# Open_Reactor_Control_System_-_Machine_In.net
KiCad netlist of a schematic drawn in Altium Designer
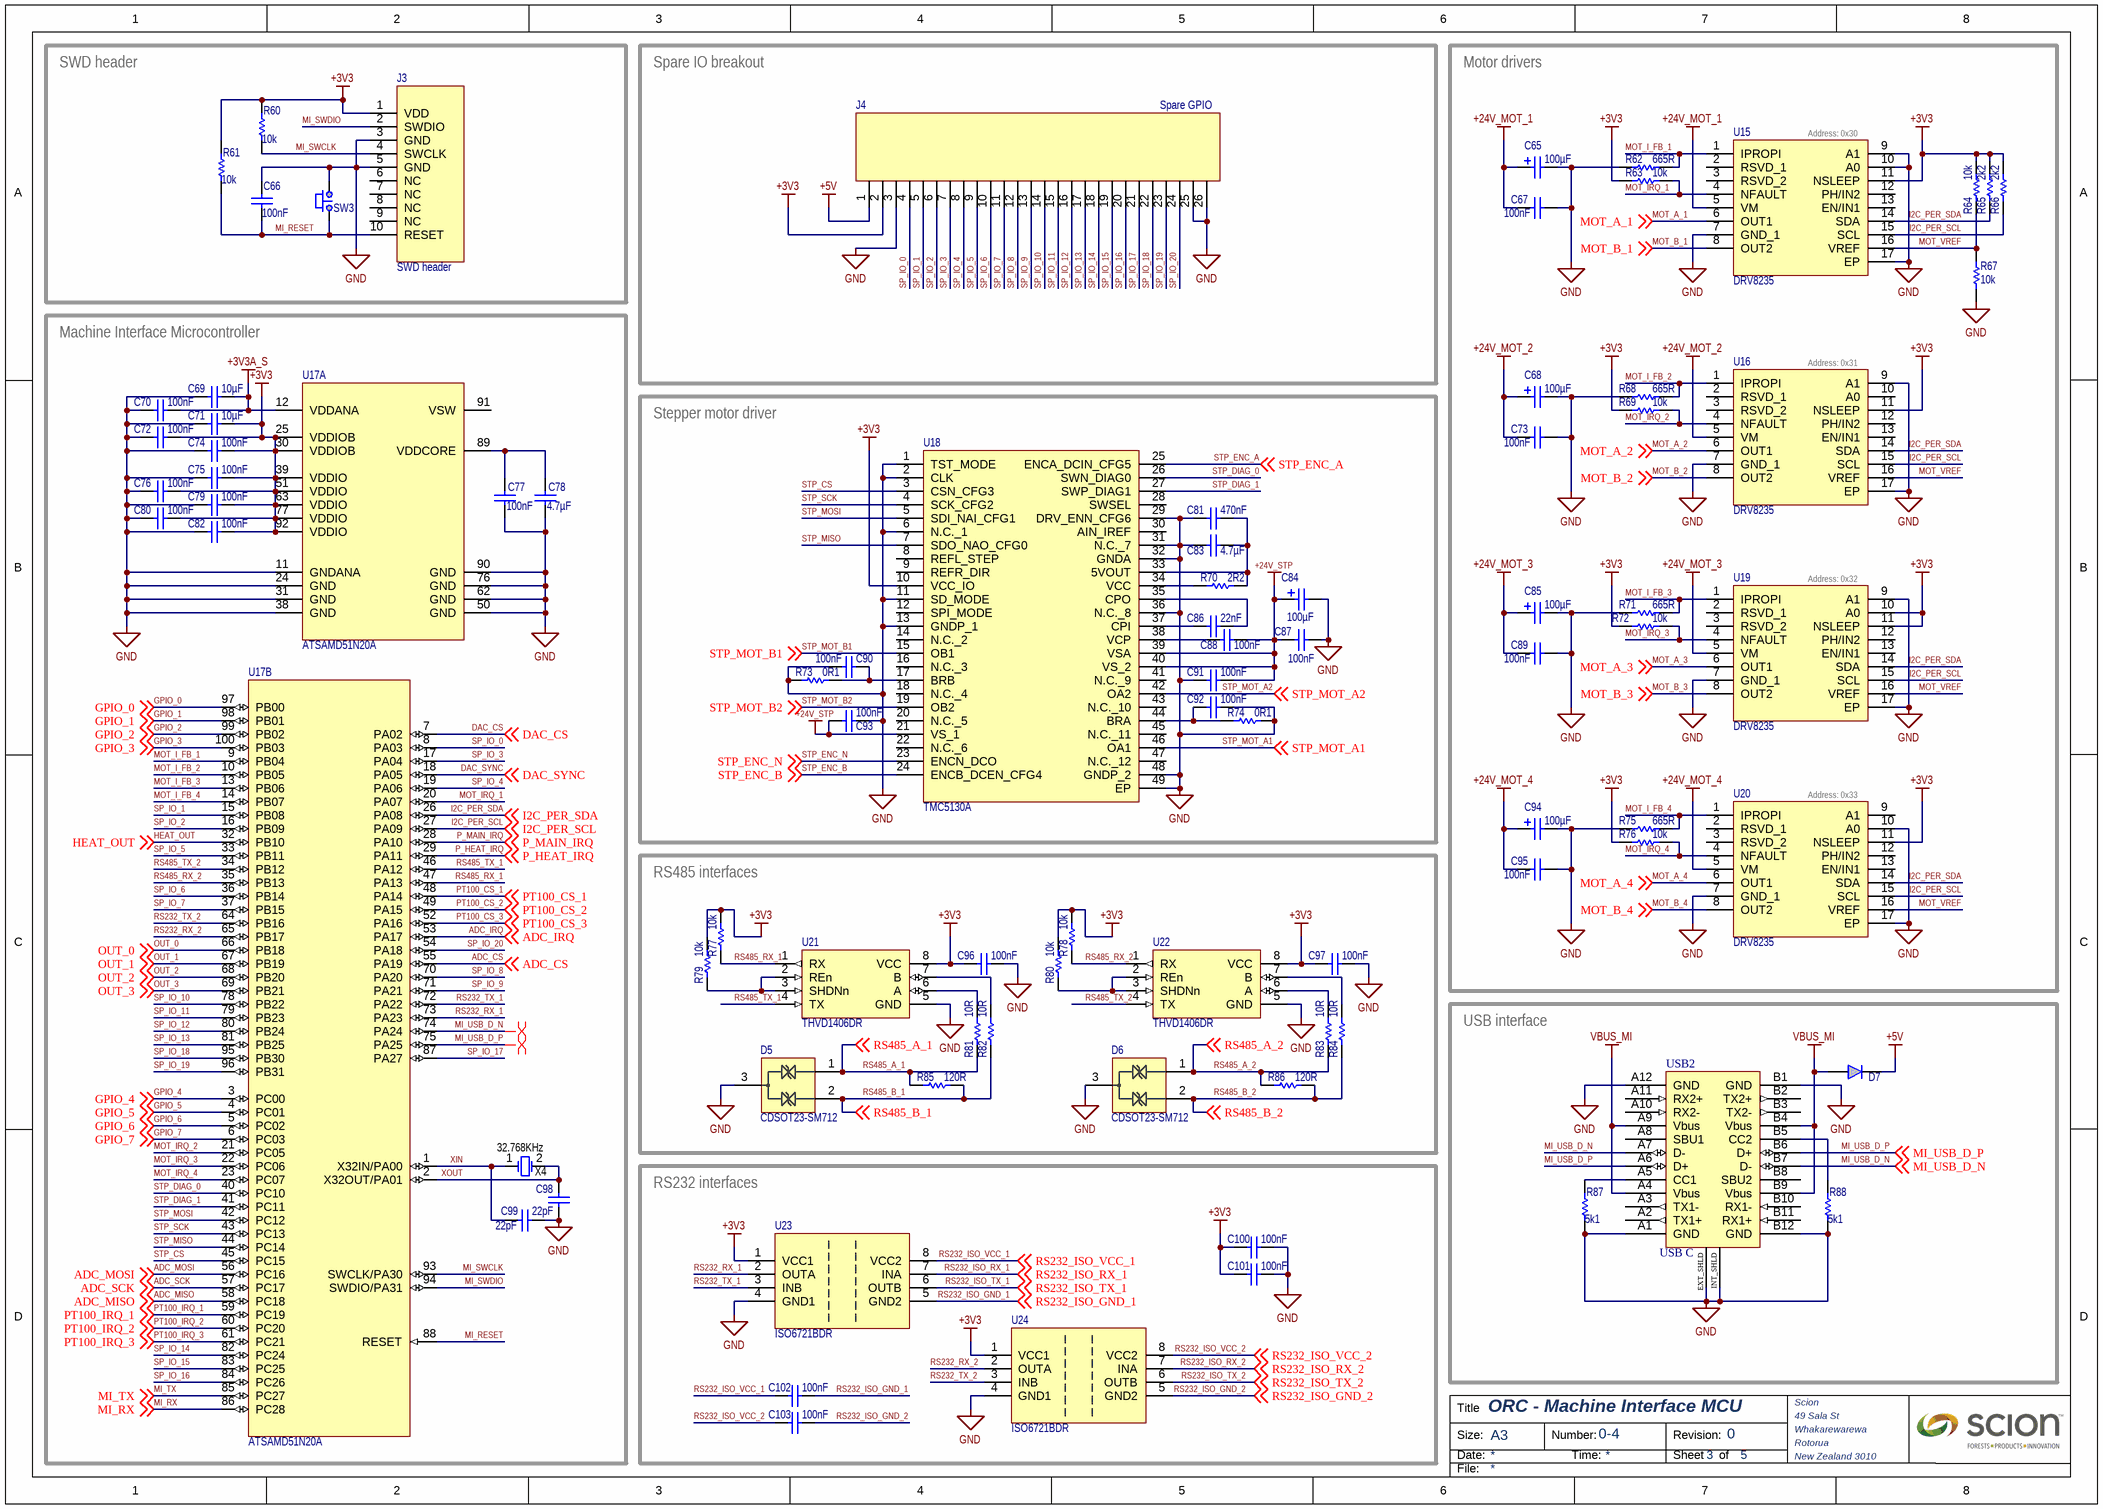
[diagram p0: Open Reactor Control System - Machine Interface MCU.SchDoc]

(export (version "E")
  (design (tool "Eeschema 10.0.6"))
  (components
    (comp (ref "C65")
      (value "Capacitor Electrolytic")
      (footprint "CAP_PANA_F12_SIZE")
      (description "SMD Electrolytic Capacitor")
      (fields (field (name "ALTIUM_VALUE") "100µF"))
      (libsource (lib "Scion Research") (part "CMP-001-00084-1"))
    )
    (comp (ref "C66")
      (value "100nF")
      (footprint "0603_CAP")
      (description "SMD Capacitor")
      (fields (field (name "Comment") "Capacitor"))
      (libsource (lib "Scion Research") (part "CMP-019-00005-2"))
    )
    (comp (ref "C67")
      (value "100nF")
      (footprint "0603_CAP")
      (description "SMD Capacitor")
      (fields (field (name "Comment") "Capacitor"))
      (libsource (lib "Scion Research") (part "CMP-019-00005-2"))
    )
    (comp (ref "C68")
      (value "Capacitor Electrolytic")
      (footprint "CAP_PANA_F12_SIZE")
      (description "SMD Electrolytic Capacitor")
      (fields (field (name "ALTIUM_VALUE") "100µF"))
      (libsource (lib "Scion Research") (part "CMP-001-00084-1"))
    )
    (comp (ref "C69")
      (value "10µF")
      (footprint "0603_CAP")
      (description "SMD Capacitor")
      (fields (field (name "Comment") "Capacitor"))
      (libsource (lib "Scion Research") (part "CMP-019-00005-2"))
    )
    (comp (ref "C70")
      (value "100nF")
      (footprint "0402_CAP")
      (description "SMD Capacitor")
      (fields (field (name "Comment") "Capacitor"))
      (libsource (lib "Scion Research") (part "CMP-019-00005-2"))
    )
    (comp (ref "C71")
      (value "10µF")
      (footprint "0603_CAP")
      (description "SMD Capacitor")
      (fields (field (name "Comment") "Capacitor"))
      (libsource (lib "Scion Research") (part "CMP-019-00005-2"))
    )
    (comp (ref "C72")
      (value "100nF")
      (footprint "0402_CAP")
      (description "SMD Capacitor")
      (fields (field (name "Comment") "Capacitor"))
      (libsource (lib "Scion Research") (part "CMP-019-00005-2"))
    )
    (comp (ref "C73")
      (value "100nF")
      (footprint "0603_CAP")
      (description "SMD Capacitor")
      (fields (field (name "Comment") "Capacitor"))
      (libsource (lib "Scion Research") (part "CMP-019-00005-2"))
    )
    (comp (ref "C74")
      (value "100nF")
      (footprint "0402_CAP")
      (description "SMD Capacitor")
      (fields (field (name "Comment") "Capacitor"))
      (libsource (lib "Scion Research") (part "CMP-019-00005-2"))
    )
    (comp (ref "C75")
      (value "100nF")
      (footprint "0402_CAP")
      (description "SMD Capacitor")
      (fields (field (name "Comment") "Capacitor"))
      (libsource (lib "Scion Research") (part "CMP-019-00005-2"))
    )
    (comp (ref "C76")
      (value "100nF")
      (footprint "0402_CAP")
      (description "SMD Capacitor")
      (fields (field (name "Comment") "Capacitor"))
      (libsource (lib "Scion Research") (part "CMP-019-00005-2"))
    )
    (comp (ref "C77")
      (value "100nF")
      (footprint "0402_CAP")
      (description "SMD Capacitor")
      (fields (field (name "Comment") "Capacitor"))
      (libsource (lib "Scion Research") (part "CMP-019-00005-2"))
    )
    (comp (ref "C78")
      (value "4.7µF")
      (footprint "0603_CAP")
      (description "SMD Capacitor")
      (fields (field (name "Comment") "Capacitor"))
      (libsource (lib "Scion Research") (part "CMP-019-00005-2"))
    )
    (comp (ref "C79")
      (value "100nF")
      (footprint "0402_CAP")
      (description "SMD Capacitor")
      (fields (field (name "Comment") "Capacitor"))
      (libsource (lib "Scion Research") (part "CMP-019-00005-2"))
    )
    (comp (ref "C80")
      (value "100nF")
      (footprint "0402_CAP")
      (description "SMD Capacitor")
      (fields (field (name "Comment") "Capacitor"))
      (libsource (lib "Scion Research") (part "CMP-019-00005-2"))
    )
    (comp (ref "C81")
      (value "470nF")
      (footprint "0603_CAP")
      (description "SMD Capacitor")
      (fields (field (name "Comment") "Capacitor"))
      (libsource (lib "Scion Research") (part "CMP-019-00005-2"))
    )
    (comp (ref "C82")
      (value "100nF")
      (footprint "0402_CAP")
      (description "SMD Capacitor")
      (fields (field (name "Comment") "Capacitor"))
      (libsource (lib "Scion Research") (part "CMP-019-00005-2"))
    )
    (comp (ref "C83")
      (value "4.7µF")
      (footprint "0603_CAP")
      (description "SMD Capacitor")
      (fields (field (name "Comment") "Capacitor"))
      (libsource (lib "Scion Research") (part "CMP-019-00005-2"))
    )
    (comp (ref "C84")
      (value "Capacitor Electrolytic")
      (footprint "CAP_PANA_F12_SIZE")
      (description "SMD Electrolytic Capacitor")
      (fields (field (name "ALTIUM_VALUE") "100µF"))
      (libsource (lib "Scion Research") (part "CMP-001-00084-1"))
    )
    (comp (ref "C85")
      (value "Capacitor Electrolytic")
      (footprint "CAP_PANA_F12_SIZE")
      (description "SMD Electrolytic Capacitor")
      (fields (field (name "ALTIUM_VALUE") "100µF"))
      (libsource (lib "Scion Research") (part "CMP-001-00084-1"))
    )
    (comp (ref "C86")
      (value "22nF")
      (footprint "0603_CAP")
      (description "SMD Capacitor")
      (fields (field (name "Comment") "Capacitor"))
      (libsource (lib "Scion Research") (part "CMP-019-00005-2"))
    )
    (comp (ref "C87")
      (value "100nF")
      (footprint "0603_CAP")
      (description "SMD Capacitor")
      (fields (field (name "Comment") "Capacitor"))
      (libsource (lib "Scion Research") (part "CMP-019-00005-2"))
    )
    (comp (ref "C88")
      (value "100nF")
      (footprint "0603_CAP")
      (description "SMD Capacitor")
      (fields (field (name "Comment") "Capacitor"))
      (libsource (lib "Scion Research") (part "CMP-019-00005-2"))
    )
    (comp (ref "C89")
      (value "100nF")
      (footprint "0603_CAP")
      (description "SMD Capacitor")
      (fields (field (name "Comment") "Capacitor"))
      (libsource (lib "Scion Research") (part "CMP-019-00005-2"))
    )
    (comp (ref "C90")
      (value "100nF")
      (footprint "0603_CAP")
      (description "SMD Capacitor")
      (fields (field (name "Comment") "Capacitor"))
      (libsource (lib "Scion Research") (part "CMP-019-00005-2"))
    )
    (comp (ref "C91")
      (value "100nF")
      (footprint "0603_CAP")
      (description "SMD Capacitor")
      (fields (field (name "Comment") "Capacitor"))
      (libsource (lib "Scion Research") (part "CMP-019-00005-2"))
    )
    (comp (ref "C92")
      (value "100nF")
      (footprint "0603_CAP")
      (description "SMD Capacitor")
      (fields (field (name "Comment") "Capacitor"))
      (libsource (lib "Scion Research") (part "CMP-019-00005-2"))
    )
    (comp (ref "C93")
      (value "100nF")
      (footprint "0603_CAP")
      (description "SMD Capacitor")
      (fields (field (name "Comment") "Capacitor"))
      (libsource (lib "Scion Research") (part "CMP-019-00005-2"))
    )
    (comp (ref "C94")
      (value "Capacitor Electrolytic")
      (footprint "CAP_PANA_F12_SIZE")
      (description "SMD Electrolytic Capacitor")
      (fields (field (name "ALTIUM_VALUE") "100µF"))
      (libsource (lib "Scion Research") (part "CMP-001-00084-1"))
    )
    (comp (ref "C95")
      (value "100nF")
      (footprint "0603_CAP")
      (description "SMD Capacitor")
      (fields (field (name "Comment") "Capacitor"))
      (libsource (lib "Scion Research") (part "CMP-019-00005-2"))
    )
    (comp (ref "C96")
      (value "100nF")
      (footprint "0603_CAP")
      (description "SMD Capacitor")
      (fields (field (name "Comment") "Capacitor"))
      (libsource (lib "Scion Research") (part "CMP-019-00005-2"))
    )
    (comp (ref "C97")
      (value "100nF")
      (footprint "0603_CAP")
      (description "SMD Capacitor")
      (fields (field (name "Comment") "Capacitor"))
      (libsource (lib "Scion Research") (part "CMP-019-00005-2"))
    )
    (comp (ref "C98")
      (value "22pF")
      (footprint "0402_CAP")
      (description "SMD Capacitor")
      (fields (field (name "Comment") "Capacitor"))
      (libsource (lib "Scion Research") (part "CMP-019-00005-2"))
    )
    (comp (ref "C99")
      (value "22pF")
      (footprint "0402_CAP")
      (description "SMD Capacitor")
      (fields (field (name "Comment") "Capacitor"))
      (libsource (lib "Scion Research") (part "CMP-019-00005-2"))
    )
    (comp (ref "C100")
      (value "100nF")
      (footprint "0603_CAP")
      (description "SMD Capacitor")
      (fields (field (name "Comment") "Capacitor"))
      (libsource (lib "Scion Research") (part "CMP-019-00005-2"))
    )
    (comp (ref "C101")
      (value "100nF")
      (footprint "0603_CAP")
      (description "SMD Capacitor")
      (fields (field (name "Comment") "Capacitor"))
      (libsource (lib "Scion Research") (part "CMP-019-00005-2"))
    )
    (comp (ref "C102")
      (value "100nF")
      (footprint "0603_CAP")
      (description "SMD Capacitor")
      (fields (field (name "Comment") "Capacitor"))
      (libsource (lib "Scion Research") (part "CMP-019-00005-2"))
    )
    (comp (ref "C103")
      (value "100nF")
      (footprint "0603_CAP")
      (description "SMD Capacitor")
      (fields (field (name "Comment") "Capacitor"))
      (libsource (lib "Scion Research") (part "CMP-019-00005-2"))
    )
    (comp (ref "D5")
      (value "CDSOT23-SM712")
      (footprint "FP-SOT23-IPC_C")
      (description "Trans Voltage Suppressor Diode, 400W, 7V V(RWM), Bidirectional, 2 Element, Silicon")
      (libsource (lib "Scion Research") (part "CDSOT23-SM712"))
    )
    (comp (ref "D6")
      (value "CDSOT23-SM712")
      (footprint "FP-SOT23-IPC_C")
      (description "Trans Voltage Suppressor Diode, 400W, 7V V(RWM), Bidirectional, 2 Element, Silicon")
      (libsource (lib "Scion Research") (part "CDSOT23-SM712"))
    )
    (comp (ref "D7")
      (value "Diode")
      (footprint "SOD-123")
      (description "SMD Diode")
      (libsource (lib "Scion Research") (part "Diode"))
    )
    (comp (ref "J3")
      (value "SWD header")
      (footprint "DIP10_1.27_M_SMD")
      (description "10 Pin Connector")
      (libsource (lib "Scion Research") (part "CMP-002-00071-2"))
    )
    (comp (ref "J4")
      (value "Spare GPIO")
      (footprint "26_Pin DIL Male Header 2.54mm")
      (description "26 Pin Connector")
      (libsource (lib "Scion Research") (part "26 Pin Connector"))
    )
    (comp (ref "R60")
      (value "Resistor")
      (footprint "0603_RES")
      (description "SMD Resistor")
      (fields (field (name "ALTIUM_VALUE") "10k"))
      (libsource (lib "Scion Research") (part "CMP-009-00177-2"))
    )
    (comp (ref "R61")
      (value "Resistor")
      (footprint "0603_RES")
      (description "SMD Resistor")
      (fields (field (name "ALTIUM_VALUE") "10k"))
      (libsource (lib "Scion Research") (part "CMP-009-00177-2"))
    )
    (comp (ref "R62")
      (value "Resistor")
      (footprint "0603_RES")
      (description "SMD Resistor")
      (fields (field (name "ALTIUM_VALUE") "665R"))
      (libsource (lib "Scion Research") (part "CMP-009-00177-2"))
    )
    (comp (ref "R63")
      (value "Resistor")
      (footprint "0603_RES")
      (description "SMD Resistor")
      (fields (field (name "ALTIUM_VALUE") "10k"))
      (libsource (lib "Scion Research") (part "CMP-009-00177-2"))
    )
    (comp (ref "R64")
      (value "Resistor")
      (footprint "0603_RES")
      (description "SMD Resistor")
      (fields (field (name "ALTIUM_VALUE") "10k"))
      (libsource (lib "Scion Research") (part "CMP-009-00177-2"))
    )
    (comp (ref "R65")
      (value "Resistor")
      (footprint "0603_RES")
      (description "SMD Resistor")
      (fields (field (name "ALTIUM_VALUE") "2k2"))
      (libsource (lib "Scion Research") (part "CMP-009-00177-2"))
    )
    (comp (ref "R66")
      (value "Resistor")
      (footprint "0603_RES")
      (description "SMD Resistor")
      (fields (field (name "ALTIUM_VALUE") "2k2"))
      (libsource (lib "Scion Research") (part "CMP-009-00177-2"))
    )
    (comp (ref "R67")
      (value "Resistor")
      (footprint "0603_RES")
      (description "SMD Resistor")
      (fields (field (name "ALTIUM_VALUE") "10k"))
      (libsource (lib "Scion Research") (part "CMP-009-00177-2"))
    )
    (comp (ref "R68")
      (value "Resistor")
      (footprint "0603_RES")
      (description "SMD Resistor")
      (fields (field (name "ALTIUM_VALUE") "665R"))
      (libsource (lib "Scion Research") (part "CMP-009-00177-2"))
    )
    (comp (ref "R69")
      (value "Resistor")
      (footprint "0603_RES")
      (description "SMD Resistor")
      (fields (field (name "ALTIUM_VALUE") "10k"))
      (libsource (lib "Scion Research") (part "CMP-009-00177-2"))
    )
    (comp (ref "R70")
      (value "Resistor")
      (footprint "0603_RES")
      (description "SMD Resistor")
      (fields (field (name "ALTIUM_VALUE") "2R2"))
      (libsource (lib "Scion Research") (part "CMP-009-00177-2"))
    )
    (comp (ref "R71")
      (value "Resistor")
      (footprint "0603_RES")
      (description "SMD Resistor")
      (fields (field (name "ALTIUM_VALUE") "665R"))
      (libsource (lib "Scion Research") (part "CMP-009-00177-2"))
    )
    (comp (ref "R72")
      (value "Resistor")
      (footprint "0603_RES")
      (description "SMD Resistor")
      (fields (field (name "ALTIUM_VALUE") "10k"))
      (libsource (lib "Scion Research") (part "CMP-009-00177-2"))
    )
    (comp (ref "R73")
      (value "Resistor")
      (footprint "1206_RES")
      (description "SMD Resistor")
      (fields (field (name "ALTIUM_VALUE") "0R1"))
      (libsource (lib "Scion Research") (part "CMP-009-00177-2"))
    )
    (comp (ref "R74")
      (value "Resistor")
      (footprint "1206_RES")
      (description "SMD Resistor")
      (fields (field (name "ALTIUM_VALUE") "0R1"))
      (libsource (lib "Scion Research") (part "CMP-009-00177-2"))
    )
    (comp (ref "R75")
      (value "Resistor")
      (footprint "0603_RES")
      (description "SMD Resistor")
      (fields (field (name "ALTIUM_VALUE") "665R"))
      (libsource (lib "Scion Research") (part "CMP-009-00177-2"))
    )
    (comp (ref "R76")
      (value "Resistor")
      (footprint "0603_RES")
      (description "SMD Resistor")
      (fields (field (name "ALTIUM_VALUE") "10k"))
      (libsource (lib "Scion Research") (part "CMP-009-00177-2"))
    )
    (comp (ref "R77")
      (value "Resistor")
      (footprint "0603_RES")
      (description "SMD Resistor")
      (fields (field (name "ALTIUM_VALUE") "10k"))
      (libsource (lib "Scion Research") (part "CMP-009-00177-2"))
    )
    (comp (ref "R78")
      (value "Resistor")
      (footprint "0603_RES")
      (description "SMD Resistor")
      (fields (field (name "ALTIUM_VALUE") "10k"))
      (libsource (lib "Scion Research") (part "CMP-009-00177-2"))
    )
    (comp (ref "R79")
      (value "Resistor")
      (footprint "0603_RES")
      (description "SMD Resistor")
      (fields (field (name "ALTIUM_VALUE") "10k"))
      (libsource (lib "Scion Research") (part "CMP-009-00177-2"))
    )
    (comp (ref "R80")
      (value "Resistor")
      (footprint "0603_RES")
      (description "SMD Resistor")
      (fields (field (name "ALTIUM_VALUE") "10k"))
      (libsource (lib "Scion Research") (part "CMP-009-00177-2"))
    )
    (comp (ref "R81")
      (value "Resistor")
      (footprint "0603_RES")
      (description "SMD Resistor")
      (fields (field (name "ALTIUM_VALUE") "10R"))
      (libsource (lib "Scion Research") (part "CMP-009-00177-2"))
    )
    (comp (ref "R82")
      (value "Resistor")
      (footprint "0603_RES")
      (description "SMD Resistor")
      (fields (field (name "ALTIUM_VALUE") "10R"))
      (libsource (lib "Scion Research") (part "CMP-009-00177-2"))
    )
    (comp (ref "R83")
      (value "Resistor")
      (footprint "0603_RES")
      (description "SMD Resistor")
      (fields (field (name "ALTIUM_VALUE") "10R"))
      (libsource (lib "Scion Research") (part "CMP-009-00177-2"))
    )
    (comp (ref "R84")
      (value "Resistor")
      (footprint "0603_RES")
      (description "SMD Resistor")
      (fields (field (name "ALTIUM_VALUE") "10R"))
      (libsource (lib "Scion Research") (part "CMP-009-00177-2"))
    )
    (comp (ref "R85")
      (value "Resistor")
      (footprint "0603_RES")
      (description "SMD Resistor")
      (fields (field (name "ALTIUM_VALUE") "120R"))
      (libsource (lib "Scion Research") (part "CMP-009-00177-2"))
    )
    (comp (ref "R86")
      (value "Resistor")
      (footprint "0603_RES")
      (description "SMD Resistor")
      (fields (field (name "ALTIUM_VALUE") "120R"))
      (libsource (lib "Scion Research") (part "CMP-009-00177-2"))
    )
    (comp (ref "R87")
      (value "Resistor")
      (footprint "0603_RES")
      (description "SMD Resistor")
      (fields (field (name "ALTIUM_VALUE") "5k1"))
      (libsource (lib "Scion Research") (part "CMP-009-00177-2"))
    )
    (comp (ref "R88")
      (value "Resistor")
      (footprint "0603_RES")
      (description "SMD Resistor")
      (fields (field (name "ALTIUM_VALUE") "5k1"))
      (libsource (lib "Scion Research") (part "CMP-009-00177-2"))
    )
    (comp (ref "SW3")
      (value "EVP-AAN02Q")
      (footprint "FP-EVP-AAN02Q-MFG")
      (description "Switch Tactile N.O. SPST Rectangular Button J-Bend 0.02A 15VDC 100000Cycles 5N SMD T/R")
      (libsource (lib "Scion Research") (part "67890d47754ac483cb1d3ba3be74b6c"))
    )
    (comp (ref "U15")
      (value "DRV8235")
      (footprint "DRV8235-Footprint-1")
      (libsource (lib "Scion Research") (part "DRV8235-Symbol-1"))
    )
    (comp (ref "U16")
      (value "DRV8235")
      (footprint "DRV8235-Footprint-1")
      (libsource (lib "Scion Research") (part "DRV8235-Symbol-1"))
    )
    (comp (ref "U17")
      (value "ATSAMD51N20A")
      (footprint "FP-C04-110-IPC_C")
      (description "RISC Microcontroller, 32-Bit, FLASH, 120MHz, CMOS, PQFP100")
      (libsource (lib "Scion Research") (part "ATSAMD51N20A-AU-Symbol-1"))
    )
    (comp (ref "U18")
      (value "TMC5130A")
      (footprint "TMC5130A-Footprint-1")
      (libsource (lib "Scion Research") (part "TMC5130A-Symbol-1"))
    )
    (comp (ref "U19")
      (value "DRV8235")
      (footprint "DRV8235-Footprint-1")
      (libsource (lib "Scion Research") (part "DRV8235-Symbol-1"))
    )
    (comp (ref "U20")
      (value "DRV8235")
      (footprint "DRV8235-Footprint-1")
      (libsource (lib "Scion Research") (part "DRV8235-Symbol-1"))
    )
    (comp (ref "U21")
      (value "THVD1406DR")
      (footprint "SOIC127P600X175-8N")
      (description "Line Transceiver, 1 Func, 1 Driver, 1 Rcvr, PDSO8")
      (libsource (lib "Scion Research") (part "THVD1406DR-Symbol-1"))
    )
    (comp (ref "U22")
      (value "THVD1406DR")
      (footprint "SOIC127P600X175-8N")
      (description "Line Transceiver, 1 Func, 1 Driver, 1 Rcvr, PDSO8")
      (libsource (lib "Scion Research") (part "THVD1406DR-Symbol-1"))
    )
    (comp (ref "U23")
      (value "ISO6721BDR")
      (footprint "SOIC127P600X175-8N")
      (description "Interface Circuit, CMOS, PDSO8")
      (libsource (lib "Scion Research") (part "ISO6721BDR-Symbol-1"))
    )
    (comp (ref "U24")
      (value "ISO6721BDR")
      (footprint "SOIC127P600X175-8N")
      (description "Interface Circuit, CMOS, PDSO8")
      (libsource (lib "Scion Research") (part "ISO6721BDR-Symbol-1"))
    )
    (comp (ref "USB2")
      (value "USB C")
      (footprint "GT-USB-7010ASV")
      (description "Vertical or RA Type C Usb Connector Rohs Compliant: Yes")
      (libsource (lib "Scion Research") (part "CMP-00005-5"))
    )
    (comp (ref "X4")
      (value "32.768KHz")
      (footprint "ABRA-ABS07-2_V")
      (fields (field (name "TOLERANCE") "20ppm") (field (name "MANUFACTURER") "Abracon"))
      (libsource (lib "Scion Research") (part "CMP-003-00022-1"))
    )
  )
  (nets
    (net (code "1") (name "+3V3") (class "Default")
      (node (ref "C100") (pin "2") (pinfunction "2_2") (pintype "passive"))
      (node (ref "C101") (pin "2") (pinfunction "2_2") (pintype "passive"))
      (node (ref "C71") (pin "1") (pinfunction "1_1") (pintype "passive"))
      (node (ref "C72") (pin "1") (pinfunction "1_1") (pintype "passive"))
      (node (ref "C74") (pin "1") (pinfunction "1_1") (pintype "passive"))
      (node (ref "C75") (pin "1") (pinfunction "1_1") (pintype "passive"))
      (node (ref "C76") (pin "1") (pinfunction "1_1") (pintype "passive"))
      (node (ref "C79") (pin "1") (pinfunction "1_1") (pintype "passive"))
      (node (ref "C80") (pin "1") (pinfunction "1_1") (pintype "passive"))
      (node (ref "C82") (pin "1") (pinfunction "1_1") (pintype "passive"))
      (node (ref "C96") (pin "2") (pinfunction "2_2") (pintype "passive"))
      (node (ref "C97") (pin "2") (pinfunction "2_2") (pintype "passive"))
      (node (ref "J3") (pin "1") (pinfunction "VDD_1") (pintype "passive"))
      (node (ref "J4") (pin "2") (pinfunction "2_2") (pintype "passive"))
      (node (ref "R60") (pin "1") (pinfunction "1_1") (pintype "passive"))
      (node (ref "R61") (pin "1") (pinfunction "1_1") (pintype "passive"))
      (node (ref "R63") (pin "2") (pinfunction "2_2") (pintype "passive"))
      (node (ref "R64") (pin "2") (pinfunction "2_2") (pintype "passive"))
      (node (ref "R65") (pin "1") (pinfunction "1_1") (pintype "passive"))
      (node (ref "R66") (pin "1") (pinfunction "1_1") (pintype "passive"))
      (node (ref "R69") (pin "2") (pinfunction "2_2") (pintype "passive"))
      (node (ref "R72") (pin "2") (pinfunction "2_2") (pintype "passive"))
      (node (ref "R76") (pin "2") (pinfunction "2_2") (pintype "passive"))
      (node (ref "R77") (pin "1") (pinfunction "1_1") (pintype "passive"))
      (node (ref "R78") (pin "1") (pinfunction "1_1") (pintype "passive"))
      (node (ref "R79") (pin "1") (pinfunction "1_1") (pintype "passive"))
      (node (ref "R80") (pin "1") (pinfunction "1_1") (pintype "passive"))
      (node (ref "U15") (pin "11") (pinfunction "NSLEEP_11") (pintype "passive"))
      (node (ref "U16") (pin "11") (pinfunction "NSLEEP_11") (pintype "passive"))
      (node (ref "U17") (pin "25") (pinfunction "VDDIOB_25") (pintype "power_in"))
      (node (ref "U17") (pin "30") (pinfunction "VDDIOB_30") (pintype "power_in"))
      (node (ref "U17") (pin "39") (pinfunction "VDDIO_39") (pintype "power_in"))
      (node (ref "U17") (pin "51") (pinfunction "VDDIO_51") (pintype "power_in"))
      (node (ref "U17") (pin "63") (pinfunction "VDDIO_63") (pintype "power_in"))
      (node (ref "U17") (pin "77") (pinfunction "VDDIO_77") (pintype "power_in"))
      (node (ref "U17") (pin "92") (pinfunction "VDDIO_92") (pintype "power_in"))
      (node (ref "U18") (pin "10") (pinfunction "VCC_IO_10") (pintype "passive"))
      (node (ref "U19") (pin "10") (pinfunction "A0_10") (pintype "passive"))
      (node (ref "U19") (pin "11") (pinfunction "NSLEEP_11") (pintype "passive"))
      (node (ref "U20") (pin "11") (pinfunction "NSLEEP_11") (pintype "passive"))
      (node (ref "U21") (pin "8") (pinfunction "VCC_8") (pintype "power_in"))
      (node (ref "U22") (pin "8") (pinfunction "VCC_8") (pintype "power_in"))
      (node (ref "U23") (pin "1") (pinfunction "VCC1_1") (pintype "passive"))
      (node (ref "U24") (pin "1") (pinfunction "VCC1_1") (pintype "passive"))
    )
    (net (code "2") (name "+3V3A_S") (class "Default")
      (node (ref "C69") (pin "1") (pinfunction "1_1") (pintype "passive"))
      (node (ref "C70") (pin "1") (pinfunction "1_1") (pintype "passive"))
      (node (ref "U17") (pin "12") (pinfunction "VDDANA_12") (pintype "power_in"))
    )
    (net (code "3") (name "+5V") (class "Default")
      (node (ref "D7") (pin "1") (pinfunction "K_1") (pintype "passive"))
      (node (ref "J4") (pin "1") (pinfunction "1_1") (pintype "passive"))
    )
    (net (code "4") (name "+24V_MOT_1") (class "Default")
      (node (ref "C65") (pin "1") (pinfunction "1_1") (pintype "passive"))
      (node (ref "C67") (pin "1") (pinfunction "1_1") (pintype "passive"))
      (node (ref "U15") (pin "5") (pinfunction "VM_5") (pintype "passive"))
    )
    (net (code "5") (name "+24V_MOT_2") (class "Default")
      (node (ref "C68") (pin "1") (pinfunction "1_1") (pintype "passive"))
      (node (ref "C73") (pin "1") (pinfunction "1_1") (pintype "passive"))
      (node (ref "U16") (pin "5") (pinfunction "VM_5") (pintype "passive"))
    )
    (net (code "6") (name "+24V_MOT_3") (class "Default")
      (node (ref "C85") (pin "1") (pinfunction "1_1") (pintype "passive"))
      (node (ref "C89") (pin "1") (pinfunction "1_1") (pintype "passive"))
      (node (ref "U19") (pin "5") (pinfunction "VM_5") (pintype "passive"))
    )
    (net (code "7") (name "+24V_MOT_4") (class "Default")
      (node (ref "C94") (pin "1") (pinfunction "1_1") (pintype "passive"))
      (node (ref "C95") (pin "1") (pinfunction "1_1") (pintype "passive"))
      (node (ref "U20") (pin "5") (pinfunction "VM_5") (pintype "passive"))
    )
    (net (code "8") (name "+24V_STP") (class "Default")
      (node (ref "C84") (pin "1") (pinfunction "1_1") (pintype "passive"))
      (node (ref "C87") (pin "1") (pinfunction "1_1") (pintype "passive"))
      (node (ref "C88") (pin "1") (pinfunction "1_1") (pintype "passive"))
      (node (ref "C91") (pin "2") (pinfunction "2_2") (pintype "passive"))
      (node (ref "C93") (pin "1") (pinfunction "1_1") (pintype "passive"))
      (node (ref "U18") (pin "21") (pinfunction "VS_1_21") (pintype "passive"))
      (node (ref "U18") (pin "39") (pinfunction "VSA_39") (pintype "passive"))
      (node (ref "U18") (pin "40") (pinfunction "VS_2_40") (pintype "passive"))
    )
    (net (code "9") (name "/MI_RESET") (class "Default")
      (node (ref "C66") (pin "2") (pinfunction "2_2") (pintype "passive"))
      (node (ref "J3") (pin "10") (pinfunction "RESET_10") (pintype "passive"))
      (node (ref "R61") (pin "2") (pinfunction "2_2") (pintype "passive"))
      (node (ref "SW3") (pin "1") (pinfunction "1_1") (pintype "passive"))
      (node (ref "U17") (pin "88") (pinfunction "RESET_88") (pintype "input"))
    )
    (net (code "10") (name "/MI_SWCLK") (class "Default")
      (node (ref "J3") (pin "4") (pinfunction "SWCLK_4") (pintype "passive"))
      (node (ref "R60") (pin "2") (pinfunction "2_2") (pintype "passive"))
      (node (ref "U17") (pin "93") (pinfunction "SWCLK/PA30_93") (pintype "bidirectional"))
    )
    (net (code "11") (name "/MI_SWDIO") (class "Default")
      (node (ref "J3") (pin "2") (pinfunction "SWDIO_2") (pintype "passive"))
      (node (ref "U17") (pin "94") (pinfunction "SWDIO/PA31_94") (pintype "bidirectional"))
    )
    (net (code "12") (name "/MOT_IRQ_1") (class "Default")
      (node (ref "R63") (pin "1") (pinfunction "1_1") (pintype "passive"))
      (node (ref "U15") (pin "4") (pinfunction "NFAULT_4") (pintype "passive"))
      (node (ref "U17") (pin "20") (pinfunction "PA07_20") (pintype "bidirectional"))
    )
    (net (code "13") (name "/MOT_IRQ_2") (class "Default")
      (node (ref "R69") (pin "1") (pinfunction "1_1") (pintype "passive"))
      (node (ref "U16") (pin "4") (pinfunction "NFAULT_4") (pintype "passive"))
      (node (ref "U17") (pin "21") (pinfunction "PC05_21") (pintype "bidirectional"))
    )
    (net (code "14") (name "/MOT_IRQ_3") (class "Default")
      (node (ref "R72") (pin "1") (pinfunction "1_1") (pintype "passive"))
      (node (ref "U17") (pin "22") (pinfunction "PC06_22") (pintype "bidirectional"))
      (node (ref "U19") (pin "4") (pinfunction "NFAULT_4") (pintype "passive"))
    )
    (net (code "15") (name "/MOT_IRQ_4") (class "Default")
      (node (ref "R76") (pin "1") (pinfunction "1_1") (pintype "passive"))
      (node (ref "U17") (pin "23") (pinfunction "PC07_23") (pintype "bidirectional"))
      (node (ref "U20") (pin "4") (pinfunction "NFAULT_4") (pintype "passive"))
    )
    (net (code "16") (name "/MOT_I_FB_1") (class "Default")
      (node (ref "R62") (pin "2") (pinfunction "2_2") (pintype "passive"))
      (node (ref "U15") (pin "1") (pinfunction "IPROPI_1") (pintype "passive"))
      (node (ref "U17") (pin "9") (pinfunction "PB04_9") (pintype "bidirectional"))
    )
    (net (code "17") (name "/MOT_I_FB_2") (class "Default")
      (node (ref "R68") (pin "2") (pinfunction "2_2") (pintype "passive"))
      (node (ref "U16") (pin "1") (pinfunction "IPROPI_1") (pintype "passive"))
      (node (ref "U17") (pin "10") (pinfunction "PB05_10") (pintype "bidirectional"))
    )
    (net (code "18") (name "/MOT_I_FB_3") (class "Default")
      (node (ref "R71") (pin "2") (pinfunction "2_2") (pintype "passive"))
      (node (ref "U17") (pin "13") (pinfunction "PB06_13") (pintype "bidirectional"))
      (node (ref "U19") (pin "1") (pinfunction "IPROPI_1") (pintype "passive"))
    )
    (net (code "19") (name "/MOT_I_FB_4") (class "Default")
      (node (ref "R75") (pin "2") (pinfunction "2_2") (pintype "passive"))
      (node (ref "U17") (pin "14") (pinfunction "PB07_14") (pintype "bidirectional"))
      (node (ref "U20") (pin "1") (pinfunction "IPROPI_1") (pintype "passive"))
    )
    (net (code "20") (name "/MOT_VREF") (class "Default")
      (node (ref "R64") (pin "1") (pinfunction "1_1") (pintype "passive"))
      (node (ref "R67") (pin "2") (pinfunction "2_2") (pintype "passive"))
      (node (ref "U15") (pin "16") (pinfunction "VREF_16") (pintype "passive"))
      (node (ref "U16") (pin "16") (pinfunction "VREF_16") (pintype "passive"))
      (node (ref "U19") (pin "16") (pinfunction "VREF_16") (pintype "passive"))
      (node (ref "U20") (pin "16") (pinfunction "VREF_16") (pintype "passive"))
    )
    (net (code "21") (name "/RS232_RX_1") (class "Default")
      (node (ref "U17") (pin "73") (pinfunction "PA23_73") (pintype "bidirectional"))
      (node (ref "U23") (pin "2") (pinfunction "OUTA_2") (pintype "passive"))
    )
    (net (code "22") (name "/RS232_RX_2") (class "Default")
      (node (ref "U17") (pin "65") (pinfunction "PB17_65") (pintype "bidirectional"))
      (node (ref "U24") (pin "2") (pinfunction "OUTA_2") (pintype "passive"))
    )
    (net (code "23") (name "/RS232_TX_1") (class "Default")
      (node (ref "U17") (pin "72") (pinfunction "PA22_72") (pintype "bidirectional"))
      (node (ref "U23") (pin "3") (pinfunction "INB_3") (pintype "passive"))
    )
    (net (code "24") (name "/RS232_TX_2") (class "Default")
      (node (ref "U17") (pin "64") (pinfunction "PB16_64") (pintype "bidirectional"))
      (node (ref "U24") (pin "3") (pinfunction "INB_3") (pintype "passive"))
    )
    (net (code "25") (name "/RS485_RX_1") (class "Default")
      (node (ref "R77") (pin "2") (pinfunction "2_2") (pintype "passive"))
      (node (ref "U17") (pin "47") (pinfunction "PA13_47") (pintype "bidirectional"))
      (node (ref "U21") (pin "1") (pinfunction "RX_1") (pintype "output"))
    )
    (net (code "26") (name "/RS485_RX_2") (class "Default")
      (node (ref "R78") (pin "2") (pinfunction "2_2") (pintype "passive"))
      (node (ref "U17") (pin "35") (pinfunction "PB13_35") (pintype "bidirectional"))
      (node (ref "U22") (pin "1") (pinfunction "RX_1") (pintype "output"))
    )
    (net (code "27") (name "/RS485_TX_1") (class "Default")
      (node (ref "U17") (pin "46") (pinfunction "PA12_46") (pintype "bidirectional"))
      (node (ref "U21") (pin "4") (pinfunction "TX_4") (pintype "input"))
    )
    (net (code "28") (name "/RS485_TX_2") (class "Default")
      (node (ref "U17") (pin "34") (pinfunction "PB12_34") (pintype "bidirectional"))
      (node (ref "U22") (pin "4") (pinfunction "TX_4") (pintype "input"))
    )
    (net (code "29") (name "/SP_IO_0") (class "Default")
      (node (ref "J4") (pin "4") (pinfunction "4_4") (pintype "passive"))
      (node (ref "U17") (pin "8") (pinfunction "PA03_8") (pintype "bidirectional"))
    )
    (net (code "30") (name "/SP_IO_1") (class "Default")
      (node (ref "J4") (pin "5") (pinfunction "5_5") (pintype "passive"))
      (node (ref "U17") (pin "15") (pinfunction "PB08_15") (pintype "bidirectional"))
    )
    (net (code "31") (name "/SP_IO_2") (class "Default")
      (node (ref "J4") (pin "6") (pinfunction "6_6") (pintype "passive"))
      (node (ref "U17") (pin "16") (pinfunction "PB09_16") (pintype "bidirectional"))
    )
    (net (code "32") (name "/SP_IO_3") (class "Default")
      (node (ref "J4") (pin "7") (pinfunction "7_7") (pintype "passive"))
      (node (ref "U17") (pin "17") (pinfunction "PA04_17") (pintype "bidirectional"))
    )
    (net (code "33") (name "/SP_IO_4") (class "Default")
      (node (ref "J4") (pin "8") (pinfunction "8_8") (pintype "passive"))
      (node (ref "U17") (pin "19") (pinfunction "PA06_19") (pintype "bidirectional"))
    )
    (net (code "34") (name "/SP_IO_5") (class "Default")
      (node (ref "J4") (pin "9") (pinfunction "9_9") (pintype "passive"))
      (node (ref "U17") (pin "33") (pinfunction "PB11_33") (pintype "bidirectional"))
    )
    (net (code "35") (name "/SP_IO_6") (class "Default")
      (node (ref "J4") (pin "10") (pinfunction "10_10") (pintype "passive"))
      (node (ref "U17") (pin "36") (pinfunction "PB14_36") (pintype "bidirectional"))
    )
    (net (code "36") (name "/SP_IO_7") (class "Default")
      (node (ref "J4") (pin "11") (pinfunction "11_11") (pintype "passive"))
      (node (ref "U17") (pin "37") (pinfunction "PB15_37") (pintype "bidirectional"))
    )
    (net (code "37") (name "/SP_IO_8") (class "Default")
      (node (ref "J4") (pin "12") (pinfunction "12_12") (pintype "passive"))
      (node (ref "U17") (pin "70") (pinfunction "PA20_70") (pintype "bidirectional"))
    )
    (net (code "38") (name "/SP_IO_9") (class "Default")
      (node (ref "J4") (pin "13") (pinfunction "13_13") (pintype "passive"))
      (node (ref "U17") (pin "71") (pinfunction "PA21_71") (pintype "bidirectional"))
    )
    (net (code "39") (name "/SP_IO_10") (class "Default")
      (node (ref "J4") (pin "14") (pinfunction "14_14") (pintype "passive"))
      (node (ref "U17") (pin "78") (pinfunction "PB22_78") (pintype "bidirectional"))
    )
    (net (code "40") (name "/SP_IO_11") (class "Default")
      (node (ref "J4") (pin "15") (pinfunction "15_15") (pintype "passive"))
      (node (ref "U17") (pin "79") (pinfunction "PB23_79") (pintype "bidirectional"))
    )
    (net (code "41") (name "/SP_IO_12") (class "Default")
      (node (ref "J4") (pin "16") (pinfunction "16_16") (pintype "passive"))
      (node (ref "U17") (pin "80") (pinfunction "PB24_80") (pintype "bidirectional"))
    )
    (net (code "42") (name "/SP_IO_13") (class "Default")
      (node (ref "J4") (pin "17") (pinfunction "17_17") (pintype "passive"))
      (node (ref "U17") (pin "81") (pinfunction "PB25_81") (pintype "bidirectional"))
    )
    (net (code "43") (name "/SP_IO_14") (class "Default")
      (node (ref "J4") (pin "18") (pinfunction "18_18") (pintype "passive"))
      (node (ref "U17") (pin "82") (pinfunction "PC24_82") (pintype "bidirectional"))
    )
    (net (code "44") (name "/SP_IO_15") (class "Default")
      (node (ref "J4") (pin "19") (pinfunction "19_19") (pintype "passive"))
      (node (ref "U17") (pin "83") (pinfunction "PC25_83") (pintype "bidirectional"))
    )
    (net (code "45") (name "/SP_IO_16") (class "Default")
      (node (ref "J4") (pin "20") (pinfunction "20_20") (pintype "passive"))
      (node (ref "U17") (pin "84") (pinfunction "PC26_84") (pintype "bidirectional"))
    )
    (net (code "46") (name "/SP_IO_17") (class "Default")
      (node (ref "J4") (pin "21") (pinfunction "21_21") (pintype "passive"))
      (node (ref "U17") (pin "87") (pinfunction "PA27_87") (pintype "bidirectional"))
    )
    (net (code "47") (name "/SP_IO_18") (class "Default")
      (node (ref "J4") (pin "22") (pinfunction "22_22") (pintype "passive"))
      (node (ref "U17") (pin "95") (pinfunction "PB30_95") (pintype "bidirectional"))
    )
    (net (code "48") (name "/SP_IO_19") (class "Default")
      (node (ref "J4") (pin "23") (pinfunction "23_23") (pintype "passive"))
      (node (ref "U17") (pin "96") (pinfunction "PB31_96") (pintype "bidirectional"))
    )
    (net (code "49") (name "/SP_IO_20") (class "Default")
      (node (ref "J4") (pin "24") (pinfunction "24_24") (pintype "passive"))
      (node (ref "U17") (pin "54") (pinfunction "PA18_54") (pintype "bidirectional"))
    )
    (net (code "50") (name "/STP_CS") (class "Default")
      (node (ref "U17") (pin "45") (pinfunction "PC15_45") (pintype "bidirectional"))
      (node (ref "U18") (pin "3") (pinfunction "CSN_CFG3_3") (pintype "passive"))
    )
    (net (code "51") (name "/STP_DIAG_0") (class "Default")
      (node (ref "U17") (pin "40") (pinfunction "PC10_40") (pintype "bidirectional"))
      (node (ref "U18") (pin "26") (pinfunction "SWN_DIAG0_26") (pintype "passive"))
    )
    (net (code "52") (name "/STP_DIAG_1") (class "Default")
      (node (ref "U17") (pin "41") (pinfunction "PC11_41") (pintype "bidirectional"))
      (node (ref "U18") (pin "27") (pinfunction "SWP_DIAG1_27") (pintype "passive"))
    )
    (net (code "53") (name "/STP_MISO") (class "Default")
      (node (ref "U17") (pin "44") (pinfunction "PC14_44") (pintype "bidirectional"))
      (node (ref "U18") (pin "7") (pinfunction "SDO_NAO_CFG0_7") (pintype "passive"))
    )
    (net (code "54") (name "/STP_MOSI") (class "Default")
      (node (ref "U17") (pin "42") (pinfunction "PC12_42") (pintype "bidirectional"))
      (node (ref "U18") (pin "5") (pinfunction "SDI_NAI_CFG1_5") (pintype "passive"))
    )
    (net (code "55") (name "/STP_SCK") (class "Default")
      (node (ref "U17") (pin "43") (pinfunction "PC13_43") (pintype "bidirectional"))
      (node (ref "U18") (pin "4") (pinfunction "SCK_CFG2_4") (pintype "passive"))
    )
    (net (code "56") (name "/XIN") (class "Default")
      (node (ref "C99") (pin "2") (pinfunction "2_2") (pintype "passive"))
      (node (ref "U17") (pin "1") (pinfunction "X32IN/PA00_1") (pintype "bidirectional"))
      (node (ref "X4") (pin "1") (pinfunction "OSC1_1") (pintype "passive"))
    )
    (net (code "57") (name "/XOUT") (class "Default")
      (node (ref "C98") (pin "1") (pinfunction "1_1") (pintype "passive"))
      (node (ref "U17") (pin "2") (pinfunction "X32OUT/PA01_2") (pintype "bidirectional"))
      (node (ref "X4") (pin "2") (pinfunction "OSC2_2") (pintype "passive"))
    )
    (net (code "58") (name "ADC_CS") (class "Default")
      (node (ref "U17") (pin "55") (pinfunction "PA19_55") (pintype "bidirectional"))
    )
    (net (code "59") (name "ADC_IRQ") (class "Default")
      (node (ref "U17") (pin "53") (pinfunction "PA17_53") (pintype "bidirectional"))
    )
    (net (code "60") (name "ADC_MISO") (class "Default")
      (node (ref "U17") (pin "58") (pinfunction "PC18_58") (pintype "bidirectional"))
    )
    (net (code "61") (name "ADC_MOSI") (class "Default")
      (node (ref "U17") (pin "56") (pinfunction "PC16_56") (pintype "bidirectional"))
    )
    (net (code "62") (name "ADC_SCK") (class "Default")
      (node (ref "U17") (pin "57") (pinfunction "PC17_57") (pintype "bidirectional"))
    )
    (net (code "63") (name "DAC_CS") (class "Default")
      (node (ref "U17") (pin "7") (pinfunction "PA02_7") (pintype "bidirectional"))
    )
    (net (code "64") (name "DAC_SYNC") (class "Default")
      (node (ref "U17") (pin "18") (pinfunction "PA05_18") (pintype "bidirectional"))
    )
    (net (code "65") (name "GND") (class "Default")
      (node (ref "C100") (pin "1") (pinfunction "1_1") (pintype "passive"))
      (node (ref "C101") (pin "1") (pinfunction "1_1") (pintype "passive"))
      (node (ref "C65") (pin "2") (pinfunction "2_2") (pintype "passive"))
      (node (ref "C66") (pin "1") (pinfunction "1_1") (pintype "passive"))
      (node (ref "C67") (pin "2") (pinfunction "2_2") (pintype "passive"))
      (node (ref "C68") (pin "2") (pinfunction "2_2") (pintype "passive"))
      (node (ref "C69") (pin "2") (pinfunction "2_2") (pintype "passive"))
      (node (ref "C70") (pin "2") (pinfunction "2_2") (pintype "passive"))
      (node (ref "C71") (pin "2") (pinfunction "2_2") (pintype "passive"))
      (node (ref "C72") (pin "2") (pinfunction "2_2") (pintype "passive"))
      (node (ref "C73") (pin "2") (pinfunction "2_2") (pintype "passive"))
      (node (ref "C74") (pin "2") (pinfunction "2_2") (pintype "passive"))
      (node (ref "C75") (pin "2") (pinfunction "2_2") (pintype "passive"))
      (node (ref "C76") (pin "2") (pinfunction "2_2") (pintype "passive"))
      (node (ref "C77") (pin "1") (pinfunction "1_1") (pintype "passive"))
      (node (ref "C78") (pin "1") (pinfunction "1_1") (pintype "passive"))
      (node (ref "C79") (pin "2") (pinfunction "2_2") (pintype "passive"))
      (node (ref "C80") (pin "2") (pinfunction "2_2") (pintype "passive"))
      (node (ref "C81") (pin "1") (pinfunction "1_1") (pintype "passive"))
      (node (ref "C82") (pin "2") (pinfunction "2_2") (pintype "passive"))
      (node (ref "C83") (pin "2") (pinfunction "2_2") (pintype "passive"))
      (node (ref "C84") (pin "2") (pinfunction "2_2") (pintype "passive"))
      (node (ref "C85") (pin "2") (pinfunction "2_2") (pintype "passive"))
      (node (ref "C87") (pin "2") (pinfunction "2_2") (pintype "passive"))
      (node (ref "C89") (pin "2") (pinfunction "2_2") (pintype "passive"))
      (node (ref "C90") (pin "1") (pinfunction "1_1") (pintype "passive"))
      (node (ref "C91") (pin "1") (pinfunction "1_1") (pintype "passive"))
      (node (ref "C92") (pin "2") (pinfunction "2_2") (pintype "passive"))
      (node (ref "C93") (pin "2") (pinfunction "2_2") (pintype "passive"))
      (node (ref "C94") (pin "2") (pinfunction "2_2") (pintype "passive"))
      (node (ref "C95") (pin "2") (pinfunction "2_2") (pintype "passive"))
      (node (ref "C96") (pin "1") (pinfunction "1_1") (pintype "passive"))
      (node (ref "C97") (pin "1") (pinfunction "1_1") (pintype "passive"))
      (node (ref "C98") (pin "2") (pinfunction "2_2") (pintype "passive"))
      (node (ref "C99") (pin "1") (pinfunction "1_1") (pintype "passive"))
      (node (ref "D5") (pin "3") (pinfunction "3_3") (pintype "passive"))
      (node (ref "D6") (pin "3") (pinfunction "3_3") (pintype "passive"))
      (node (ref "J3") (pin "3") (pinfunction "GND_3") (pintype "passive"))
      (node (ref "J3") (pin "5") (pinfunction "GND_5") (pintype "passive"))
      (node (ref "J4") (pin "25") (pinfunction "25_25") (pintype "passive"))
      (node (ref "J4") (pin "26") (pinfunction "26_26") (pintype "passive"))
      (node (ref "J4") (pin "3") (pinfunction "3_3") (pintype "passive"))
      (node (ref "R62") (pin "1") (pinfunction "1_1") (pintype "passive"))
      (node (ref "R67") (pin "1") (pinfunction "1_1") (pintype "passive"))
      (node (ref "R68") (pin "1") (pinfunction "1_1") (pintype "passive"))
      (node (ref "R71") (pin "1") (pinfunction "1_1") (pintype "passive"))
      (node (ref "R73") (pin "2") (pinfunction "2_2") (pintype "passive"))
      (node (ref "R74") (pin "1") (pinfunction "1_1") (pintype "passive"))
      (node (ref "R75") (pin "1") (pinfunction "1_1") (pintype "passive"))
      (node (ref "R87") (pin "2") (pinfunction "2_2") (pintype "passive"))
      (node (ref "R88") (pin "2") (pinfunction "2_2") (pintype "passive"))
      (node (ref "SW3") (pin "2") (pinfunction "2_2") (pintype "passive"))
      (node (ref "U15") (pin "10") (pinfunction "A0_10") (pintype "passive"))
      (node (ref "U15") (pin "17") (pinfunction "EP_17") (pintype "passive"))
      (node (ref "U15") (pin "7") (pinfunction "GND_1_7") (pintype "passive"))
      (node (ref "U15") (pin "9") (pinfunction "A1_9") (pintype "passive"))
      (node (ref "U16") (pin "17") (pinfunction "EP_17") (pintype "passive"))
      (node (ref "U16") (pin "7") (pinfunction "GND_1_7") (pintype "passive"))
      (node (ref "U16") (pin "9") (pinfunction "A1_9") (pintype "passive"))
      (node (ref "U17") (pin "11") (pinfunction "GNDANA_11") (pintype "power_in"))
      (node (ref "U17") (pin "24") (pinfunction "GND_24") (pintype "power_in"))
      (node (ref "U17") (pin "31") (pinfunction "GND_31") (pintype "power_in"))
      (node (ref "U17") (pin "38") (pinfunction "GND_38") (pintype "power_in"))
      (node (ref "U17") (pin "50") (pinfunction "GND_50") (pintype "power_in"))
      (node (ref "U17") (pin "62") (pinfunction "GND_62") (pintype "power_in"))
      (node (ref "U17") (pin "76") (pinfunction "GND_76") (pintype "power_in"))
      (node (ref "U17") (pin "90") (pinfunction "GND_90") (pintype "power_in"))
      (node (ref "U18") (pin "1") (pinfunction "TST_MODE_1") (pintype "passive"))
      (node (ref "U18") (pin "11") (pinfunction "SD_MODE_11") (pintype "passive"))
      (node (ref "U18") (pin "13") (pinfunction "GNDP_1_13") (pintype "passive"))
      (node (ref "U18") (pin "2") (pinfunction "CLK_2") (pintype "passive"))
      (node (ref "U18") (pin "29") (pinfunction "DRV_ENN_CFG6_29") (pintype "passive"))
      (node (ref "U18") (pin "31") (pinfunction "N.C._7_31") (pintype "passive"))
      (node (ref "U18") (pin "32") (pinfunction "GNDA_32") (pintype "passive"))
      (node (ref "U18") (pin "36") (pinfunction "N.C._8_36") (pintype "passive"))
      (node (ref "U18") (pin "48") (pinfunction "GNDP_2_48") (pintype "passive"))
      (node (ref "U18") (pin "49") (pinfunction "EP_49") (pintype "passive"))
      (node (ref "U18") (pin "6") (pinfunction "N.C._1_6") (pintype "passive"))
      (node (ref "U19") (pin "17") (pinfunction "EP_17") (pintype "passive"))
      (node (ref "U19") (pin "7") (pinfunction "GND_1_7") (pintype "passive"))
      (node (ref "U19") (pin "9") (pinfunction "A1_9") (pintype "passive"))
      (node (ref "U20") (pin "10") (pinfunction "A0_10") (pintype "passive"))
      (node (ref "U20") (pin "17") (pinfunction "EP_17") (pintype "passive"))
      (node (ref "U20") (pin "7") (pinfunction "GND_1_7") (pintype "passive"))
      (node (ref "U21") (pin "5") (pinfunction "GND_5") (pintype "power_in"))
      (node (ref "U22") (pin "5") (pinfunction "GND_5") (pintype "power_in"))
      (node (ref "U23") (pin "4") (pinfunction "GND1_4") (pintype "passive"))
      (node (ref "U24") (pin "4") (pinfunction "GND1_4") (pintype "passive"))
      (node (ref "USB2") (pin "A1") (pinfunction "GND_A1") (pintype "power_in"))
      (node (ref "USB2") (pin "A12") (pinfunction "GND_A12") (pintype "power_in"))
      (node (ref "USB2") (pin "B1") (pinfunction "GND_B1") (pintype "power_in"))
      (node (ref "USB2") (pin "B12") (pinfunction "GND_B12") (pintype "power_in"))
      (node (ref "USB2") (pin "EXT_SHLD") (pintype "passive"))
      (node (ref "USB2") (pin "INT_SHLD") (pintype "passive"))
    )
    (net (code "66") (name "GPIO_0") (class "Default")
      (node (ref "U17") (pin "97") (pinfunction "PB00_97") (pintype "bidirectional"))
    )
    (net (code "67") (name "GPIO_1") (class "Default")
      (node (ref "U17") (pin "98") (pinfunction "PB01_98") (pintype "bidirectional"))
    )
    (net (code "68") (name "GPIO_2") (class "Default")
      (node (ref "U17") (pin "99") (pinfunction "PB02_99") (pintype "bidirectional"))
    )
    (net (code "69") (name "GPIO_3") (class "Default")
      (node (ref "U17") (pin "100") (pinfunction "PB03_100") (pintype "bidirectional"))
    )
    (net (code "70") (name "GPIO_4") (class "Default")
      (node (ref "U17") (pin "3") (pinfunction "PC00_3") (pintype "bidirectional"))
    )
    (net (code "71") (name "GPIO_5") (class "Default")
      (node (ref "U17") (pin "4") (pinfunction "PC01_4") (pintype "bidirectional"))
    )
    (net (code "72") (name "GPIO_6") (class "Default")
      (node (ref "U17") (pin "5") (pinfunction "PC02_5") (pintype "bidirectional"))
    )
    (net (code "73") (name "GPIO_7") (class "Default")
      (node (ref "U17") (pin "6") (pinfunction "PC03_6") (pintype "bidirectional"))
    )
    (net (code "74") (name "HEAT_OUT") (class "Default")
      (node (ref "U17") (pin "32") (pinfunction "PB10_32") (pintype "bidirectional"))
    )
    (net (code "75") (name "I2C_PER_SCL") (class "Default")
      (node (ref "R66") (pin "2") (pinfunction "2_2") (pintype "passive"))
      (node (ref "U15") (pin "15") (pinfunction "SCL_15") (pintype "passive"))
      (node (ref "U16") (pin "15") (pinfunction "SCL_15") (pintype "passive"))
      (node (ref "U17") (pin "27") (pinfunction "PA09_27") (pintype "bidirectional"))
      (node (ref "U19") (pin "15") (pinfunction "SCL_15") (pintype "passive"))
      (node (ref "U20") (pin "15") (pinfunction "SCL_15") (pintype "passive"))
    )
    (net (code "76") (name "I2C_PER_SDA") (class "Default")
      (node (ref "R65") (pin "2") (pinfunction "2_2") (pintype "passive"))
      (node (ref "U15") (pin "14") (pinfunction "SDA_14") (pintype "passive"))
      (node (ref "U16") (pin "14") (pinfunction "SDA_14") (pintype "passive"))
      (node (ref "U17") (pin "26") (pinfunction "PA08_26") (pintype "bidirectional"))
      (node (ref "U19") (pin "14") (pinfunction "SDA_14") (pintype "passive"))
      (node (ref "U20") (pin "14") (pinfunction "SDA_14") (pintype "passive"))
    )
    (net (code "77") (name "MI_RX") (class "Default")
      (node (ref "U17") (pin "86") (pinfunction "PC28_86") (pintype "bidirectional"))
    )
    (net (code "78") (name "MI_TX") (class "Default")
      (node (ref "U17") (pin "85") (pinfunction "PC27_85") (pintype "bidirectional"))
    )
    (net (code "79") (name "MI_USB_D_N") (class "Default")
      (node (ref "U17") (pin "74") (pinfunction "PA24_74") (pintype "bidirectional"))
      (node (ref "USB2") (pin "A7") (pinfunction "D-_A7") (pintype "bidirectional"))
      (node (ref "USB2") (pin "B7") (pinfunction "D-_B7") (pintype "bidirectional"))
    )
    (net (code "80") (name "MI_USB_D_P") (class "Default")
      (node (ref "U17") (pin "75") (pinfunction "PA25_75") (pintype "bidirectional"))
      (node (ref "USB2") (pin "A6") (pinfunction "D+_A6") (pintype "bidirectional"))
      (node (ref "USB2") (pin "B6") (pinfunction "D+_B6") (pintype "bidirectional"))
    )
    (net (code "81") (name "MOT_A_1") (class "Default")
      (node (ref "U15") (pin "6") (pinfunction "OUT1_6") (pintype "passive"))
    )
    (net (code "82") (name "MOT_A_2") (class "Default")
      (node (ref "U16") (pin "6") (pinfunction "OUT1_6") (pintype "passive"))
    )
    (net (code "83") (name "MOT_A_3") (class "Default")
      (node (ref "U19") (pin "6") (pinfunction "OUT1_6") (pintype "passive"))
    )
    (net (code "84") (name "MOT_A_4") (class "Default")
      (node (ref "U20") (pin "6") (pinfunction "OUT1_6") (pintype "passive"))
    )
    (net (code "85") (name "MOT_B_1") (class "Default")
      (node (ref "U15") (pin "8") (pinfunction "OUT2_8") (pintype "passive"))
    )
    (net (code "86") (name "MOT_B_2") (class "Default")
      (node (ref "U16") (pin "8") (pinfunction "OUT2_8") (pintype "passive"))
    )
    (net (code "87") (name "MOT_B_3") (class "Default")
      (node (ref "U19") (pin "8") (pinfunction "OUT2_8") (pintype "passive"))
    )
    (net (code "88") (name "MOT_B_4") (class "Default")
      (node (ref "U20") (pin "8") (pinfunction "OUT2_8") (pintype "passive"))
    )
    (net (code "89") (name "Net-(U17A-VDDCORE)") (class "Default")
      (node (ref "C77") (pin "2") (pinfunction "2_2") (pintype "passive"))
      (node (ref "C78") (pin "2") (pinfunction "2_2") (pintype "passive"))
      (node (ref "U17") (pin "89") (pinfunction "VDDCORE_89") (pintype "power_in"))
    )
    (net (code "90") (name "Net-(U18-5VOUT)") (class "Default")
      (node (ref "C81") (pin "2") (pinfunction "2_2") (pintype "passive"))
      (node (ref "C83") (pin "1") (pinfunction "1_1") (pintype "passive"))
      (node (ref "R70") (pin "1") (pinfunction "1_1") (pintype "passive"))
      (node (ref "U18") (pin "33") (pinfunction "5VOUT_33") (pintype "passive"))
    )
    (net (code "91") (name "Net-(U18-BRA)") (class "Default")
      (node (ref "C92") (pin "1") (pinfunction "1_1") (pintype "passive"))
      (node (ref "R74") (pin "2") (pinfunction "2_2") (pintype "passive"))
      (node (ref "U18") (pin "44") (pinfunction "BRA_44") (pintype "passive"))
    )
    (net (code "92") (name "Net-(U18-BRB)") (class "Default")
      (node (ref "C90") (pin "2") (pinfunction "2_2") (pintype "passive"))
      (node (ref "R73") (pin "1") (pinfunction "1_1") (pintype "passive"))
      (node (ref "U18") (pin "17") (pinfunction "BRB_17") (pintype "passive"))
    )
    (net (code "93") (name "Net-(U18-CPI)") (class "Default")
      (node (ref "C86") (pin "1") (pinfunction "1_1") (pintype "passive"))
      (node (ref "U18") (pin "37") (pinfunction "CPI_37") (pintype "passive"))
    )
    (net (code "94") (name "Net-(U18-CPO)") (class "Default")
      (node (ref "C86") (pin "2") (pinfunction "2_2") (pintype "passive"))
      (node (ref "U18") (pin "35") (pinfunction "CPO_35") (pintype "passive"))
    )
    (net (code "95") (name "Net-(U18-VCC)") (class "Default")
      (node (ref "R70") (pin "2") (pinfunction "2_2") (pintype "passive"))
      (node (ref "U18") (pin "34") (pinfunction "VCC_34") (pintype "passive"))
    )
    (net (code "96") (name "Net-(U18-VCP)") (class "Default")
      (node (ref "C88") (pin "2") (pinfunction "2_2") (pintype "passive"))
      (node (ref "U18") (pin "38") (pinfunction "VCP_38") (pintype "passive"))
    )
    (net (code "97") (name "Net-(U21-A)") (class "Default")
      (node (ref "R81") (pin "2") (pinfunction "2_2") (pintype "passive"))
      (node (ref "U21") (pin "6") (pinfunction "A_6") (pintype "bidirectional"))
    )
    (net (code "98") (name "Net-(U21-B)") (class "Default")
      (node (ref "R82") (pin "2") (pinfunction "2_2") (pintype "passive"))
      (node (ref "U21") (pin "7") (pinfunction "B_7") (pintype "bidirectional"))
    )
    (net (code "99") (name "Net-(U21-REn)") (class "Default")
      (node (ref "R79") (pin "2") (pinfunction "2_2") (pintype "passive"))
      (node (ref "U21") (pin "2") (pinfunction "REn_2") (pintype "input"))
      (node (ref "U21") (pin "3") (pinfunction "SHDNn_3") (pintype "input"))
    )
    (net (code "100") (name "Net-(U22-A)") (class "Default")
      (node (ref "R83") (pin "2") (pinfunction "2_2") (pintype "passive"))
      (node (ref "U22") (pin "6") (pinfunction "A_6") (pintype "bidirectional"))
    )
    (net (code "101") (name "Net-(U22-B)") (class "Default")
      (node (ref "R84") (pin "2") (pinfunction "2_2") (pintype "passive"))
      (node (ref "U22") (pin "7") (pinfunction "B_7") (pintype "bidirectional"))
    )
    (net (code "102") (name "Net-(U22-REn)") (class "Default")
      (node (ref "R80") (pin "2") (pinfunction "2_2") (pintype "passive"))
      (node (ref "U22") (pin "2") (pinfunction "REn_2") (pintype "input"))
      (node (ref "U22") (pin "3") (pinfunction "SHDNn_3") (pintype "input"))
    )
    (net (code "103") (name "Net-(USB2-CC1)") (class "Default")
      (node (ref "R87") (pin "1") (pinfunction "1_1") (pintype "passive"))
      (node (ref "USB2") (pin "A5") (pinfunction "CC1_A5") (pintype "passive"))
    )
    (net (code "104") (name "Net-(USB2-CC2)") (class "Default")
      (node (ref "R88") (pin "1") (pinfunction "1_1") (pintype "passive"))
      (node (ref "USB2") (pin "B5") (pinfunction "CC2_B5") (pintype "passive"))
    )
    (net (code "105") (name "OUT_0") (class "Default")
      (node (ref "U17") (pin "66") (pinfunction "PB18_66") (pintype "bidirectional"))
    )
    (net (code "106") (name "OUT_1") (class "Default")
      (node (ref "U17") (pin "67") (pinfunction "PB19_67") (pintype "bidirectional"))
    )
    (net (code "107") (name "OUT_2") (class "Default")
      (node (ref "U17") (pin "68") (pinfunction "PB20_68") (pintype "bidirectional"))
    )
    (net (code "108") (name "OUT_3") (class "Default")
      (node (ref "U17") (pin "69") (pinfunction "PB21_69") (pintype "bidirectional"))
    )
    (net (code "109") (name "PT100_CS_1") (class "Default")
      (node (ref "U17") (pin "48") (pinfunction "PA14_48") (pintype "bidirectional"))
    )
    (net (code "110") (name "PT100_CS_2") (class "Default")
      (node (ref "U17") (pin "49") (pinfunction "PA15_49") (pintype "bidirectional"))
    )
    (net (code "111") (name "PT100_CS_3") (class "Default")
      (node (ref "U17") (pin "52") (pinfunction "PA16_52") (pintype "bidirectional"))
    )
    (net (code "112") (name "PT100_IRQ_1") (class "Default")
      (node (ref "U17") (pin "59") (pinfunction "PC19_59") (pintype "bidirectional"))
    )
    (net (code "113") (name "PT100_IRQ_2") (class "Default")
      (node (ref "U17") (pin "60") (pinfunction "PC20_60") (pintype "bidirectional"))
    )
    (net (code "114") (name "PT100_IRQ_3") (class "Default")
      (node (ref "U17") (pin "61") (pinfunction "PC21_61") (pintype "bidirectional"))
    )
    (net (code "115") (name "P_HEAT_IRQ") (class "Default")
      (node (ref "U17") (pin "29") (pinfunction "PA11_29") (pintype "bidirectional"))
    )
    (net (code "116") (name "P_MAIN_IRQ") (class "Default")
      (node (ref "U17") (pin "28") (pinfunction "PA10_28") (pintype "bidirectional"))
    )
    (net (code "117") (name "RS232_ISO_GND_1") (class "Default")
      (node (ref "C102") (pin "1") (pinfunction "1_1") (pintype "passive"))
      (node (ref "U23") (pin "5") (pinfunction "GND2_5") (pintype "passive"))
    )
    (net (code "118") (name "RS232_ISO_GND_2") (class "Default")
      (node (ref "C103") (pin "1") (pinfunction "1_1") (pintype "passive"))
      (node (ref "U24") (pin "5") (pinfunction "GND2_5") (pintype "passive"))
    )
    (net (code "119") (name "RS232_ISO_RX_1") (class "Default")
      (node (ref "U23") (pin "7") (pinfunction "INA_7") (pintype "passive"))
    )
    (net (code "120") (name "RS232_ISO_RX_2") (class "Default")
      (node (ref "U24") (pin "7") (pinfunction "INA_7") (pintype "passive"))
    )
    (net (code "121") (name "RS232_ISO_TX_1") (class "Default")
      (node (ref "U23") (pin "6") (pinfunction "OUTB_6") (pintype "passive"))
    )
    (net (code "122") (name "RS232_ISO_TX_2") (class "Default")
      (node (ref "U24") (pin "6") (pinfunction "OUTB_6") (pintype "passive"))
    )
    (net (code "123") (name "RS232_ISO_VCC_1") (class "Default")
      (node (ref "C102") (pin "2") (pinfunction "2_2") (pintype "passive"))
      (node (ref "U23") (pin "8") (pinfunction "VCC2_8") (pintype "passive"))
    )
    (net (code "124") (name "RS232_ISO_VCC_2") (class "Default")
      (node (ref "C103") (pin "2") (pinfunction "2_2") (pintype "passive"))
      (node (ref "U24") (pin "8") (pinfunction "VCC2_8") (pintype "passive"))
    )
    (net (code "125") (name "RS485_A_1") (class "Default")
      (node (ref "D5") (pin "1") (pinfunction "1_1") (pintype "passive"))
      (node (ref "R81") (pin "1") (pinfunction "1_1") (pintype "passive"))
      (node (ref "R85") (pin "1") (pinfunction "1_1") (pintype "passive"))
    )
    (net (code "126") (name "RS485_A_2") (class "Default")
      (node (ref "D6") (pin "1") (pinfunction "1_1") (pintype "passive"))
      (node (ref "R83") (pin "1") (pinfunction "1_1") (pintype "passive"))
      (node (ref "R86") (pin "1") (pinfunction "1_1") (pintype "passive"))
    )
    (net (code "127") (name "RS485_B_1") (class "Default")
      (node (ref "D5") (pin "2") (pinfunction "2_2") (pintype "passive"))
      (node (ref "R82") (pin "1") (pinfunction "1_1") (pintype "passive"))
      (node (ref "R85") (pin "2") (pinfunction "2_2") (pintype "passive"))
    )
    (net (code "128") (name "RS485_B_2") (class "Default")
      (node (ref "D6") (pin "2") (pinfunction "2_2") (pintype "passive"))
      (node (ref "R84") (pin "1") (pinfunction "1_1") (pintype "passive"))
      (node (ref "R86") (pin "2") (pinfunction "2_2") (pintype "passive"))
    )
    (net (code "129") (name "STP_ENC_A") (class "Default")
      (node (ref "U18") (pin "25") (pinfunction "ENCA_DCIN_CFG5_25") (pintype "passive"))
    )
    (net (code "130") (name "STP_ENC_B") (class "Default")
      (node (ref "U18") (pin "24") (pinfunction "ENCB_DCEN_CFG4_24") (pintype "passive"))
    )
    (net (code "131") (name "STP_ENC_N") (class "Default")
      (node (ref "U18") (pin "23") (pinfunction "ENCN_DCO_23") (pintype "passive"))
    )
    (net (code "132") (name "STP_MOT_A1") (class "Default")
      (node (ref "U18") (pin "46") (pinfunction "OA1_46") (pintype "passive"))
    )
    (net (code "133") (name "STP_MOT_A2") (class "Default")
      (node (ref "U18") (pin "42") (pinfunction "OA2_42") (pintype "passive"))
    )
    (net (code "134") (name "STP_MOT_B1") (class "Default")
      (node (ref "U18") (pin "15") (pinfunction "OB1_15") (pintype "passive"))
    )
    (net (code "135") (name "STP_MOT_B2") (class "Default")
      (node (ref "U18") (pin "19") (pinfunction "OB2_19") (pintype "passive"))
    )
    (net (code "136") (name "VBUS_MI") (class "Default")
      (node (ref "D7") (pin "2") (pinfunction "A_2") (pintype "passive"))
      (node (ref "USB2") (pin "A4") (pinfunction "Vbus_A4") (pintype "power_in"))
      (node (ref "USB2") (pin "A9") (pinfunction "Vbus_A9") (pintype "power_in"))
      (node (ref "USB2") (pin "B4") (pinfunction "Vbus_B4") (pintype "power_in"))
      (node (ref "USB2") (pin "B9") (pinfunction "Vbus_B9") (pintype "power_in"))
    )
    (net (code "137") (name "unconnected-(J3-NC-Pad6)") (class "Default")
      (node (ref "J3") (pin "6") (pinfunction "NC_6") (pintype "passive"))
    )
    (net (code "138") (name "unconnected-(J3-NC-Pad7)") (class "Default")
      (node (ref "J3") (pin "7") (pinfunction "NC_7") (pintype "passive"))
    )
    (net (code "139") (name "unconnected-(J3-NC-Pad8)") (class "Default")
      (node (ref "J3") (pin "8") (pinfunction "NC_8") (pintype "passive"))
    )
    (net (code "140") (name "unconnected-(J3-NC-Pad9)") (class "Default")
      (node (ref "J3") (pin "9") (pinfunction "NC_9") (pintype "passive"))
    )
    (net (code "141") (name "unconnected-(U15-EN{slash}IN1-Pad13)") (class "Default")
      (node (ref "U15") (pin "13") (pinfunction "EN/IN1_13") (pintype "passive"))
    )
    (net (code "142") (name "unconnected-(U15-PH{slash}IN2-Pad12)") (class "Default")
      (node (ref "U15") (pin "12") (pinfunction "PH/IN2_12") (pintype "passive"))
    )
    (net (code "143") (name "unconnected-(U15-RSVD_1-Pad2)") (class "Default")
      (node (ref "U15") (pin "2") (pinfunction "RSVD_1_2") (pintype "passive"))
    )
    (net (code "144") (name "unconnected-(U15-RSVD_2-Pad3)") (class "Default")
      (node (ref "U15") (pin "3") (pinfunction "RSVD_2_3") (pintype "passive"))
    )
    (net (code "145") (name "unconnected-(U16-A0-Pad10)") (class "Default")
      (node (ref "U16") (pin "10") (pinfunction "A0_10") (pintype "passive"))
    )
    (net (code "146") (name "unconnected-(U16-EN{slash}IN1-Pad13)") (class "Default")
      (node (ref "U16") (pin "13") (pinfunction "EN/IN1_13") (pintype "passive"))
    )
    (net (code "147") (name "unconnected-(U16-PH{slash}IN2-Pad12)") (class "Default")
      (node (ref "U16") (pin "12") (pinfunction "PH/IN2_12") (pintype "passive"))
    )
    (net (code "148") (name "unconnected-(U16-RSVD_1-Pad2)") (class "Default")
      (node (ref "U16") (pin "2") (pinfunction "RSVD_1_2") (pintype "passive"))
    )
    (net (code "149") (name "unconnected-(U16-RSVD_2-Pad3)") (class "Default")
      (node (ref "U16") (pin "3") (pinfunction "RSVD_2_3") (pintype "passive"))
    )
    (net (code "150") (name "unconnected-(U17A-VSW-Pad91)") (class "Default")
      (node (ref "U17") (pin "91") (pinfunction "VSW_91") (pintype "power_in"))
    )
    (net (code "151") (name "unconnected-(U18-AIN_IREF-Pad30)") (class "Default")
      (node (ref "U18") (pin "30") (pinfunction "AIN_IREF_30") (pintype "passive"))
    )
    (net (code "152") (name "unconnected-(U18-N.C._2-Pad14)") (class "Default")
      (node (ref "U18") (pin "14") (pinfunction "N.C._2_14") (pintype "passive"))
    )
    (net (code "153") (name "unconnected-(U18-N.C._3-Pad16)") (class "Default")
      (node (ref "U18") (pin "16") (pinfunction "N.C._3_16") (pintype "passive"))
    )
    (net (code "154") (name "unconnected-(U18-N.C._4-Pad18)") (class "Default")
      (node (ref "U18") (pin "18") (pinfunction "N.C._4_18") (pintype "passive"))
    )
    (net (code "155") (name "unconnected-(U18-N.C._5-Pad20)") (class "Default")
      (node (ref "U18") (pin "20") (pinfunction "N.C._5_20") (pintype "passive"))
    )
    (net (code "156") (name "unconnected-(U18-N.C._6-Pad22)") (class "Default")
      (node (ref "U18") (pin "22") (pinfunction "N.C._6_22") (pintype "passive"))
    )
    (net (code "157") (name "unconnected-(U18-N.C._9-Pad41)") (class "Default")
      (node (ref "U18") (pin "41") (pinfunction "N.C._9_41") (pintype "passive"))
    )
    (net (code "158") (name "unconnected-(U18-N.C._10-Pad43)") (class "Default")
      (node (ref "U18") (pin "43") (pinfunction "N.C._10_43") (pintype "passive"))
    )
    (net (code "159") (name "unconnected-(U18-N.C._11-Pad45)") (class "Default")
      (node (ref "U18") (pin "45") (pinfunction "N.C._11_45") (pintype "passive"))
    )
    (net (code "160") (name "unconnected-(U18-N.C._12-Pad47)") (class "Default")
      (node (ref "U18") (pin "47") (pinfunction "N.C._12_47") (pintype "passive"))
    )
    (net (code "161") (name "unconnected-(U18-REFL_STEP-Pad8)") (class "Default")
      (node (ref "U18") (pin "8") (pinfunction "REFL_STEP_8") (pintype "passive"))
    )
    (net (code "162") (name "unconnected-(U18-REFR_DIR-Pad9)") (class "Default")
      (node (ref "U18") (pin "9") (pinfunction "REFR_DIR_9") (pintype "passive"))
    )
    (net (code "163") (name "unconnected-(U18-SPI_MODE-Pad12)") (class "Default")
      (node (ref "U18") (pin "12") (pinfunction "SPI_MODE_12") (pintype "passive"))
    )
    (net (code "164") (name "unconnected-(U18-SWSEL-Pad28)") (class "Default")
      (node (ref "U18") (pin "28") (pinfunction "SWSEL_28") (pintype "passive"))
    )
    (net (code "165") (name "unconnected-(U19-EN{slash}IN1-Pad13)") (class "Default")
      (node (ref "U19") (pin "13") (pinfunction "EN/IN1_13") (pintype "passive"))
    )
    (net (code "166") (name "unconnected-(U19-PH{slash}IN2-Pad12)") (class "Default")
      (node (ref "U19") (pin "12") (pinfunction "PH/IN2_12") (pintype "passive"))
    )
    (net (code "167") (name "unconnected-(U19-RSVD_1-Pad2)") (class "Default")
      (node (ref "U19") (pin "2") (pinfunction "RSVD_1_2") (pintype "passive"))
    )
    (net (code "168") (name "unconnected-(U19-RSVD_2-Pad3)") (class "Default")
      (node (ref "U19") (pin "3") (pinfunction "RSVD_2_3") (pintype "passive"))
    )
    (net (code "169") (name "unconnected-(U20-A1-Pad9)") (class "Default")
      (node (ref "U20") (pin "9") (pinfunction "A1_9") (pintype "passive"))
    )
    (net (code "170") (name "unconnected-(U20-EN{slash}IN1-Pad13)") (class "Default")
      (node (ref "U20") (pin "13") (pinfunction "EN/IN1_13") (pintype "passive"))
    )
    (net (code "171") (name "unconnected-(U20-PH{slash}IN2-Pad12)") (class "Default")
      (node (ref "U20") (pin "12") (pinfunction "PH/IN2_12") (pintype "passive"))
    )
    (net (code "172") (name "unconnected-(U20-RSVD_1-Pad2)") (class "Default")
      (node (ref "U20") (pin "2") (pinfunction "RSVD_1_2") (pintype "passive"))
    )
    (net (code "173") (name "unconnected-(U20-RSVD_2-Pad3)") (class "Default")
      (node (ref "U20") (pin "3") (pinfunction "RSVD_2_3") (pintype "passive"))
    )
    (net (code "174") (name "unconnected-(USB2-RX1+-PadB11)") (class "Default")
      (node (ref "USB2") (pin "B11") (pinfunction "RX1+_B11") (pintype "input"))
    )
    (net (code "175") (name "unconnected-(USB2-RX1--PadB10)") (class "Default")
      (node (ref "USB2") (pin "B10") (pinfunction "RX1-_B10") (pintype "input"))
    )
    (net (code "176") (name "unconnected-(USB2-RX2+-PadA11)") (class "Default")
      (node (ref "USB2") (pin "A11") (pinfunction "RX2+_A11") (pintype "input"))
    )
    (net (code "177") (name "unconnected-(USB2-RX2--PadA10)") (class "Default")
      (node (ref "USB2") (pin "A10") (pinfunction "RX2-_A10") (pintype "input"))
    )
    (net (code "178") (name "unconnected-(USB2-SBU1-PadA8)") (class "Default")
      (node (ref "USB2") (pin "A8") (pinfunction "SBU1_A8") (pintype "passive"))
    )
    (net (code "179") (name "unconnected-(USB2-SBU2-PadB8)") (class "Default")
      (node (ref "USB2") (pin "B8") (pinfunction "SBU2_B8") (pintype "passive"))
    )
    (net (code "180") (name "unconnected-(USB2-TX1+-PadA2)") (class "Default")
      (node (ref "USB2") (pin "A2") (pinfunction "TX1+_A2") (pintype "output"))
    )
    (net (code "181") (name "unconnected-(USB2-TX1--PadA3)") (class "Default")
      (node (ref "USB2") (pin "A3") (pinfunction "TX1-_A3") (pintype "output"))
    )
    (net (code "182") (name "unconnected-(USB2-TX2+-PadB2)") (class "Default")
      (node (ref "USB2") (pin "B2") (pinfunction "TX2+_B2") (pintype "output"))
    )
    (net (code "183") (name "unconnected-(USB2-TX2--PadB3)") (class "Default")
      (node (ref "USB2") (pin "B3") (pinfunction "TX2-_B3") (pintype "output"))
    )
  )
)
